# tiny13_charlie4_50mm_boosted_optical.net
KiCad netlist of a schematic drawn in EAGLE
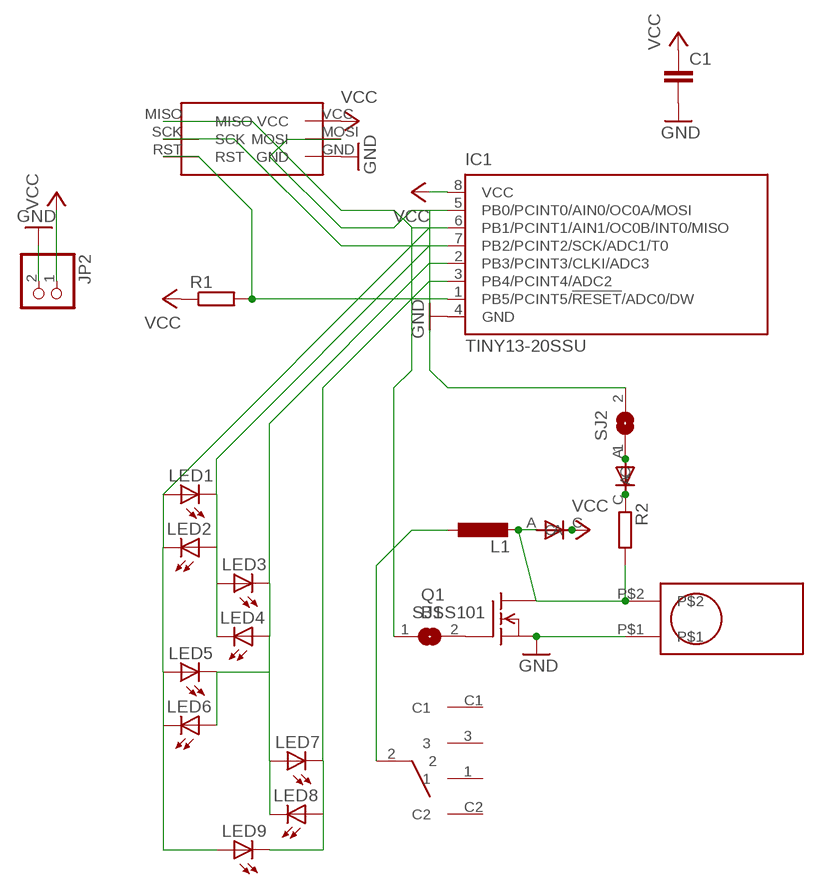
[diagram p0: schematic, sheet 1]

(export (version "E")
  (design (tool "Eeschema 10.0.6"))
  (components
    (comp (ref "C1")
      (value "C-EU025-025X050")
      (footprint "eagle-import:C025-025X050")
      (libsource (lib "eagle-import") (part "C-EU025-025X050"))
    )
    (comp (ref "IC1")
      (value "TINY13-20SSU")
      (footprint "eagle-import:8S1")
      (fields (field (name "MPN") "ATTINY13-20SSU"))
      (libsource (lib "eagle-import") (part "TINY13SSU-20"))
    )
    (comp (ref "JP2")
      (value "PINHD-1X2")
      (footprint "eagle-import:1X02")
      (libsource (lib "eagle-import") (part "PINHD-1X2"))
    )
    (comp (ref "L1")
      (value "L-EU0204/5")
      (footprint "eagle-import:0204_5")
      (libsource (lib "eagle-import") (part "L-EU0204/5"))
    )
    (comp (ref "LED1")
      (value "LED3MM")
      (footprint "eagle-import:LED3MM")
      (libsource (lib "eagle-import") (part "LED3MM"))
    )
    (comp (ref "LED2")
      (value "LED3MM")
      (footprint "eagle-import:LED3MM")
      (libsource (lib "eagle-import") (part "LED3MM"))
    )
    (comp (ref "LED3")
      (value "LED3MM")
      (footprint "eagle-import:LED3MM")
      (libsource (lib "eagle-import") (part "LED3MM"))
    )
    (comp (ref "LED4")
      (value "LED3MM")
      (footprint "eagle-import:LED3MM")
      (libsource (lib "eagle-import") (part "LED3MM"))
    )
    (comp (ref "LED5")
      (value "LED3MM")
      (footprint "eagle-import:LED3MM")
      (libsource (lib "eagle-import") (part "LED3MM"))
    )
    (comp (ref "LED6")
      (value "LED3MM")
      (footprint "eagle-import:LED3MM")
      (libsource (lib "eagle-import") (part "LED3MM"))
    )
    (comp (ref "LED7")
      (value "LED3MM")
      (footprint "eagle-import:LED3MM")
      (libsource (lib "eagle-import") (part "LED3MM"))
    )
    (comp (ref "LED8")
      (value "LED3MM")
      (footprint "eagle-import:LED3MM")
      (libsource (lib "eagle-import") (part "LED3MM"))
    )
    (comp (ref "LED9")
      (value "LED3MM")
      (footprint "eagle-import:LED3MM")
      (libsource (lib "eagle-import") (part "LED3MM"))
    )
    (comp (ref "Q1")
      (value "BSS101")
      (footprint "eagle-import:TO92")
      (libsource (lib "eagle-import") (part "BSS101"))
    )
    (comp (ref "R1")
      (value "R-EU_0204/5")
      (footprint "eagle-import:0204_5")
      (libsource (lib "eagle-import") (part "R-EU_0204/5"))
    )
    (comp (ref "R2")
      (value "R-EU_0204/5")
      (footprint "eagle-import:0204_5")
      (libsource (lib "eagle-import") (part "R-EU_0204/5"))
    )
    (comp (ref "SJ1") (value "SJ") (footprint "eagle-import:SJ") (libsource (lib "eagle-import") (part "SJ")))
    (comp (ref "SJ2") (value "SJ") (footprint "eagle-import:SJ") (libsource (lib "eagle-import") (part "SJ")))
    (comp (ref "U$1")
      (value "TILT_SWITCH_MECHANICAL")
      (footprint "eagle-import:TILT_SWITCH_MECHANICAL")
      (libsource (lib "eagle-import") (part "TILT_SWITCH_MECHANICAL"))
    )
    (comp (ref "U$2")
      (value "AVR_ISP_6_PIN_1X6_SMT_CONTACT_PROGRAMMER")
      (footprint "eagle-import:CONTACT_ISP_PROGRAMMER_1X6_ATMEL")
      (libsource (lib "eagle-import") (part "AVR_ISP_6_PIN_1X6_SMT_CONTACT_PROGRAMMER"))
    )
    (comp (ref "U$3")
      (value "D-6")
      (footprint "eagle-import:D-7.5")
      (libsource (lib "eagle-import") (part "D-6"))
    )
    (comp (ref "U$4")
      (value "D-6")
      (footprint "eagle-import:D-7.5")
      (libsource (lib "eagle-import") (part "D-6"))
    )
    (comp (ref "U$5")
      (value "SWITCH")
      (footprint "eagle-import:SWITCH")
      (libsource (lib "eagle-import") (part "SWITCH"))
    )
  )
  (nets
    (net (code "1") (name "GND") (class "Default")
      (node (ref "C1") (pin "2") (pinfunction "2_2") (pintype "passive"))
      (node (ref "IC1") (pin "4") (pinfunction "GND_4") (pintype "power_in"))
      (node (ref "JP2") (pin "2") (pinfunction "2_2") (pintype "passive"))
      (node (ref "Q1") (pin "1") (pinfunction "S_1") (pintype "passive"))
      (node (ref "U$1") (pin "P$1") (pinfunction "P$1_P$1") (pintype "bidirectional"))
      (node (ref "U$2") (pin "GND") (pinfunction "GND_GND") (pintype "bidirectional"))
    )
    (net (code "2") (name "Net-(IC1-PB0{slash}PCINT0{slash}AIN0{slash}OC0A{slash}MOSI)") (class "Default")
      (node (ref "IC1") (pin "5") (pinfunction "PB0/PCINT0/AIN0/OC0A/MOSI_5") (pintype "bidirectional"))
      (node (ref "SJ2") (pin "2") (pinfunction "2_2") (pintype "passive"))
      (node (ref "U$2") (pin "MOSI") (pinfunction "MOSI_MOSI") (pintype "bidirectional"))
    )
    (net (code "3") (name "Net-(IC1-PB1{slash}PCINT1{slash}AIN1{slash}OC0B{slash}INT0{slash}MISO)") (class "Default")
      (node (ref "IC1") (pin "6") (pinfunction "PB1/PCINT1/AIN1/OC0B/INT0/MISO_6") (pintype "bidirectional"))
      (node (ref "LED1") (pin "A") (pinfunction "A_A") (pintype "passive"))
      (node (ref "LED2") (pin "K") (pinfunction "C_K") (pintype "passive"))
      (node (ref "LED5") (pin "A") (pinfunction "A_A") (pintype "passive"))
      (node (ref "LED6") (pin "K") (pinfunction "C_K") (pintype "passive"))
      (node (ref "LED9") (pin "A") (pinfunction "A_A") (pintype "passive"))
      (node (ref "SJ1") (pin "1") (pinfunction "1_1") (pintype "passive"))
      (node (ref "U$2") (pin "MISO") (pinfunction "MISO_MISO") (pintype "bidirectional"))
    )
    (net (code "4") (name "Net-(IC1-PB2{slash}PCINT2{slash}SCK{slash}ADC1{slash}T0)") (class "Default")
      (node (ref "IC1") (pin "7") (pinfunction "PB2/PCINT2/SCK/ADC1/T0_7") (pintype "bidirectional"))
      (node (ref "LED1") (pin "K") (pinfunction "C_K") (pintype "passive"))
      (node (ref "LED2") (pin "A") (pinfunction "A_A") (pintype "passive"))
      (node (ref "LED3") (pin "A") (pinfunction "A_A") (pintype "passive"))
      (node (ref "LED4") (pin "K") (pinfunction "C_K") (pintype "passive"))
      (node (ref "U$2") (pin "SCK") (pinfunction "SCK_SCK") (pintype "bidirectional"))
    )
    (net (code "5") (name "Net-(IC1-PB3{slash}PCINT3{slash}CLKI{slash}ADC3)") (class "Default")
      (node (ref "IC1") (pin "2") (pinfunction "PB3/PCINT3/CLKI/ADC3_2") (pintype "bidirectional"))
      (node (ref "LED3") (pin "K") (pinfunction "C_K") (pintype "passive"))
      (node (ref "LED4") (pin "A") (pinfunction "A_A") (pintype "passive"))
      (node (ref "LED5") (pin "K") (pinfunction "C_K") (pintype "passive"))
      (node (ref "LED6") (pin "A") (pinfunction "A_A") (pintype "passive"))
      (node (ref "LED7") (pin "A") (pinfunction "A_A") (pintype "passive"))
      (node (ref "LED8") (pin "K") (pinfunction "C_K") (pintype "passive"))
    )
    (net (code "6") (name "Net-(IC1-PB4{slash}PCINT4{slash}ADC2)") (class "Default")
      (node (ref "IC1") (pin "3") (pinfunction "PB4/PCINT4/ADC2_3") (pintype "bidirectional"))
      (node (ref "LED7") (pin "K") (pinfunction "C_K") (pintype "passive"))
      (node (ref "LED8") (pin "A") (pinfunction "A_A") (pintype "passive"))
      (node (ref "LED9") (pin "K") (pinfunction "C_K") (pintype "passive"))
    )
    (net (code "7") (name "Net-(IC1-PB5{slash}PCINT5{slash}~{RESET}{slash}ADC0{slash}DW)") (class "Default")
      (node (ref "IC1") (pin "1") (pinfunction "PB5/PCINT5/~{RESET}/ADC0/DW_1") (pintype "bidirectional"))
      (node (ref "R1") (pin "2") (pinfunction "2_2") (pintype "passive"))
      (node (ref "U$2") (pin "RST") (pinfunction "RST_RST") (pintype "bidirectional"))
    )
    (net (code "8") (name "Net-(L1-Pad1)") (class "Default")
      (node (ref "L1") (pin "1") (pinfunction "1_1") (pintype "passive"))
      (node (ref "U$5") (pin "2") (pinfunction "2_2") (pintype "bidirectional"))
    )
    (net (code "9") (name "Net-(Q1-D)") (class "Default")
      (node (ref "L1") (pin "2") (pinfunction "2_2") (pintype "passive"))
      (node (ref "Q1") (pin "3") (pinfunction "D_3") (pintype "passive"))
      (node (ref "R2") (pin "2") (pinfunction "2_2") (pintype "passive"))
      (node (ref "U$1") (pin "P$2") (pinfunction "P$2_P$2") (pintype "bidirectional"))
      (node (ref "U$3") (pin "A") (pinfunction "A_A") (pintype "bidirectional"))
    )
    (net (code "10") (name "Net-(Q1-G)") (class "Default")
      (node (ref "Q1") (pin "2") (pinfunction "G_2") (pintype "passive"))
      (node (ref "SJ1") (pin "2") (pinfunction "2_2") (pintype "passive"))
    )
    (net (code "11") (name "Net-(R2-Pad1)") (class "Default")
      (node (ref "R2") (pin "1") (pinfunction "1_1") (pintype "passive"))
      (node (ref "U$4") (pin "C") (pinfunction "C_C") (pintype "bidirectional"))
    )
    (net (code "12") (name "Net-(SJ2-Pad1)") (class "Default")
      (node (ref "SJ2") (pin "1") (pinfunction "1_1") (pintype "passive"))
      (node (ref "U$4") (pin "A") (pinfunction "A_A") (pintype "bidirectional"))
    )
    (net (code "13") (name "VCC") (class "Default")
      (node (ref "C1") (pin "1") (pinfunction "1_1") (pintype "passive"))
      (node (ref "IC1") (pin "8") (pinfunction "VCC_8") (pintype "power_in"))
      (node (ref "JP2") (pin "1") (pinfunction "1_1") (pintype "passive"))
      (node (ref "R1") (pin "1") (pinfunction "1_1") (pintype "passive"))
      (node (ref "U$2") (pin "VCC") (pinfunction "VCC_VCC") (pintype "bidirectional"))
      (node (ref "U$3") (pin "C") (pinfunction "C_C") (pintype "bidirectional"))
    )
    (net (code "14") (name "unconnected-(U$5-Pad1)") (class "Default")
      (node (ref "U$5") (pin "1") (pinfunction "1_1") (pintype "bidirectional"))
    )
    (net (code "15") (name "unconnected-(U$5-Pad3)") (class "Default")
      (node (ref "U$5") (pin "3") (pinfunction "3_3") (pintype "bidirectional"))
    )
    (net (code "16") (name "unconnected-(U$5-PadC1)") (class "Default")
      (node (ref "U$5") (pin "C1") (pinfunction "C1_C1") (pintype "bidirectional"))
    )
    (net (code "17") (name "unconnected-(U$5-PadC2)") (class "Default")
      (node (ref "U$5") (pin "C2") (pinfunction "C2_C2") (pintype "bidirectional"))
    )
  )
)
